# main.net
KiCad netlist of a schematic drawn in Altium Designer
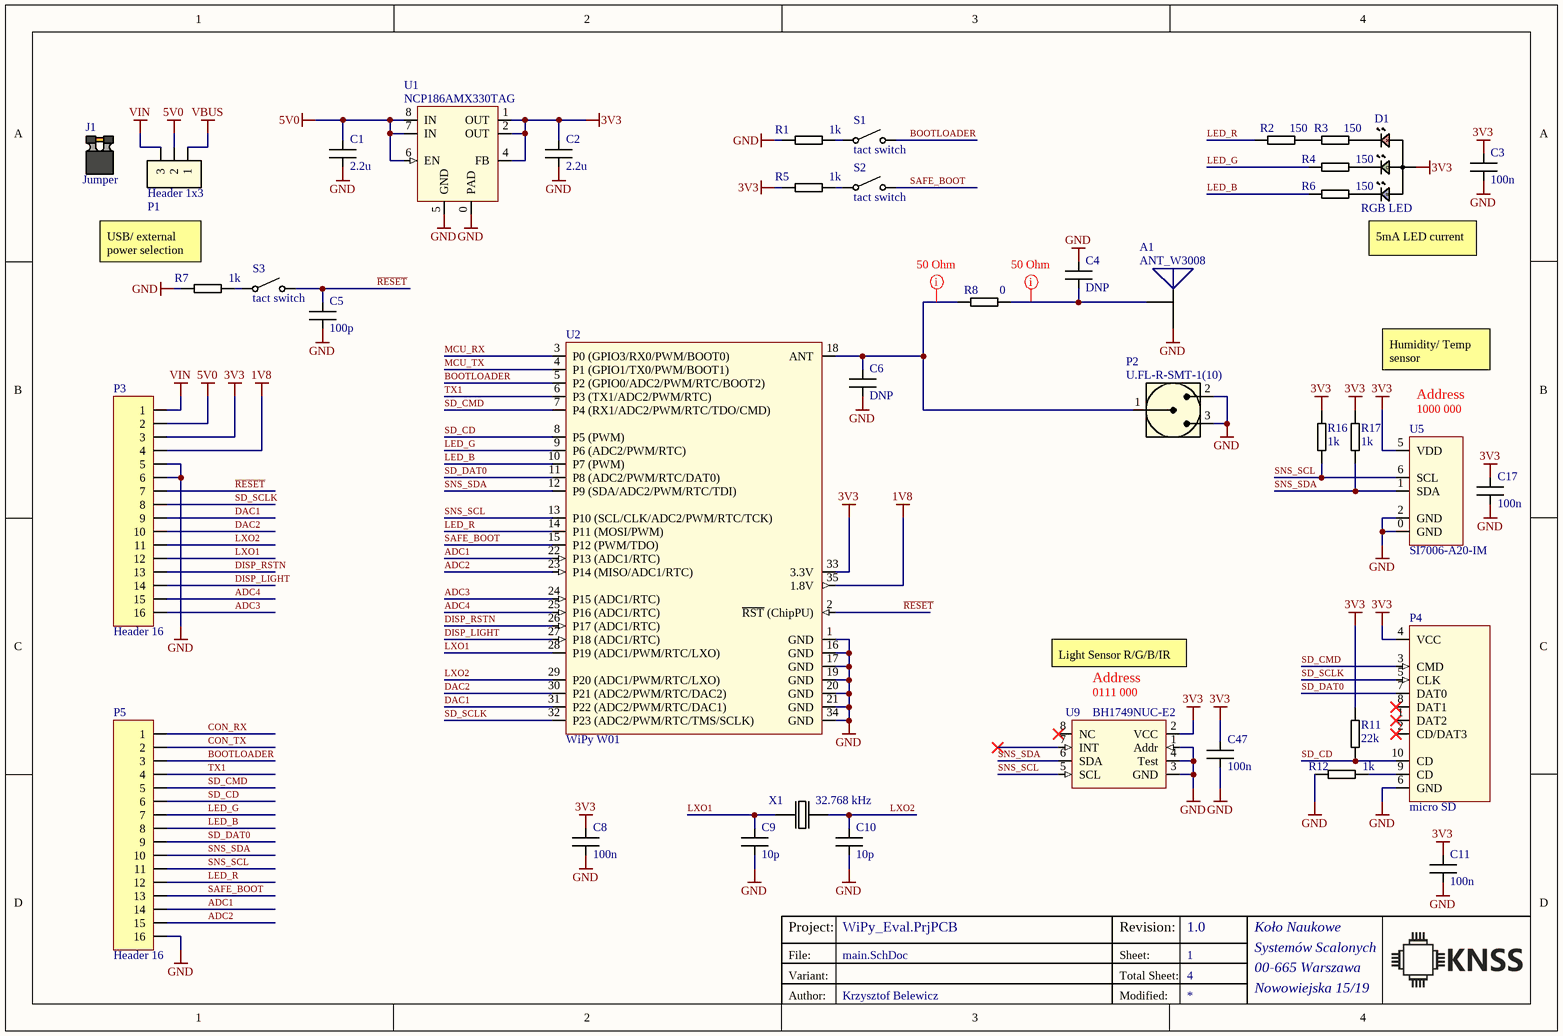
[diagram p0: main.SchDoc]

(export (version "E")
  (design (tool "Eeschema 10.0.6"))
  (components
    (comp (ref "A1")
      (value "ANT_W3008")
      (footprint "W3008")
      (description "Bluetooth / WLAN / WiFi  Ceramic Chip Antenna W x L x H (3.2 x 1.6 x 1.1 mm)")
      (libsource (lib "LIBRARY_SCH") (part "ANT_W3008"))
    )
    (comp (ref "C1")
      (value "2.2u")
      (footprint "CAPC1005N")
      (description "0402 SMD Capacitor")
      (fields (field (name "TOLERANCE") "10%") (field (name "Comment") "Capacitor"))
      (libsource (lib "RLC") (part "Capacitor"))
    )
    (comp (ref "C2")
      (value "2.2u")
      (footprint "CAPC1005N")
      (description "0402 SMD Capacitor")
      (fields (field (name "TOLERANCE") "10%") (field (name "Comment") "Capacitor"))
      (libsource (lib "RLC") (part "Capacitor"))
    )
    (comp (ref "C3")
      (value "100n")
      (footprint "CAPC1005N")
      (description "0402 SMD Capacitor")
      (fields (field (name "TOLERANCE") "10%"))
      (libsource (lib "RLC") (part "Capacitor"))
    )
    (comp (ref "C4")
      (value "DNP")
      (footprint "CAPC1005N")
      (description "0402 SMD Capacitor")
      (fields (field (name "Comment") "Capacitor"))
      (libsource (lib "RLC") (part "Capacitor"))
    )
    (comp (ref "C5")
      (value "100p")
      (footprint "CAPC1005N")
      (description "0402 SMD Capacitor")
      (fields (field (name "TOLERANCE") "10%"))
      (libsource (lib "RLC") (part "Capacitor"))
    )
    (comp (ref "C6")
      (value "DNP")
      (footprint "CAPC1005N")
      (description "0402 SMD Capacitor")
      (fields (field (name "Comment") "Capacitor"))
      (libsource (lib "RLC") (part "Capacitor"))
    )
    (comp (ref "C8")
      (value "100n")
      (footprint "CAPC1005N")
      (description "0402 SMD Capacitor")
      (fields (field (name "TOLERANCE") "10%"))
      (libsource (lib "RLC") (part "Capacitor"))
    )
    (comp (ref "C9")
      (value "10p")
      (footprint "CAPC1005N")
      (description "0402 SMD Capacitor")
      (fields (field (name "TOLERANCE") "5%"))
      (libsource (lib "RLC") (part "Capacitor"))
    )
    (comp (ref "C10")
      (value "10p")
      (footprint "CAPC1005N")
      (description "0402 SMD Capacitor")
      (fields (field (name "TOLERANCE") "5%"))
      (libsource (lib "RLC") (part "Capacitor"))
    )
    (comp (ref "C11")
      (value "100n")
      (footprint "CAPC1005N")
      (description "0402 SMD Capacitor")
      (fields (field (name "TOLERANCE") "10%"))
      (libsource (lib "RLC") (part "Capacitor"))
    )
    (comp (ref "C17")
      (value "100n")
      (footprint "CAPC1005N")
      (description "0402 SMD Capacitor")
      (fields (field (name "TOLERANCE") "10%"))
      (libsource (lib "RLC") (part "Capacitor"))
    )
    (comp (ref "C47")
      (value "100n")
      (footprint "CAPC1005N")
      (description "0402 SMD Capacitor")
      (fields (field (name "TOLERANCE") "10%"))
      (libsource (lib "RLC") (part "Capacitor"))
    )
    (comp (ref "D1")
      (value "RGB LED")
      (footprint "PLCC-4")
      (description "LED; SMD; 3528,PLCC4; RGB; 3,5x2,8x1,9mm; 115°; 20mA; Common anode")
      (libsource (lib "Broadcom_LED") (part "ASMB-MTB1-0A3A2"))
    )
    (comp (ref "J1")
      (value "Jumper")
      (footprint "JUMPER-B")
      (description "1x2, 2.54mm Black header jumper")
      (libsource (lib "Ninigi_Jumpers") (part "Header Jumper Black"))
    )
    (comp (ref "P1")
      (value "Header 1x3")
      (footprint "Header 1x3, Male, 2.54mm, Straight, THT")
      (description "Pin header, 1x3, 2.54mm")
      (libsource (lib "Header") (part "Header 1x3"))
    )
    (comp (ref "P2")
      (value "U.FL-R-SMT-1(10)")
      (footprint "U.FL-R-SMT-1(10)")
      (description "Hirose UFL connector")
      (libsource (lib "Hirose") (part "U.FL-R-SMT-1(10)"))
    )
    (comp (ref "P3")
      (value "Header 16")
      (footprint "HDR1X16")
      (description "Header, 16-Pin")
      (libsource (lib "Miscellaneous Connectors") (part "Header 16"))
    )
    (comp (ref "P4")
      (value "micro SD")
      (footprint "1140084168")
      (description "Memory Card Connectors Micro SD 8 Pin PCB Gold")
      (libsource (lib "Amphenol_uSD") (part "1140084168"))
    )
    (comp (ref "P5")
      (value "Header 16")
      (footprint "HDR1X16")
      (description "Header, 16-Pin")
      (libsource (lib "Miscellaneous Connectors") (part "Header 16"))
    )
    (comp (ref "R1")
      (value "1k")
      (footprint "RESC1005N")
      (description "0402 Film SMD Resistor")
      (fields (field (name "TOLERANCE") "1%") (field (name "POWER") "0.1W"))
      (libsource (lib "RLC") (part "Resistor"))
    )
    (comp (ref "R2")
      (value "150")
      (footprint "RESC1005N")
      (description "0402 Film SMD Resistor")
      (fields (field (name "TOLERANCE") "1%") (field (name "POWER") "0.1W"))
      (libsource (lib "RLC") (part "Resistor"))
    )
    (comp (ref "R3")
      (value "150")
      (footprint "RESC1005N")
      (description "0402 Film SMD Resistor")
      (fields (field (name "TOLERANCE") "1%") (field (name "POWER") "0.1W"))
      (libsource (lib "RLC") (part "Resistor"))
    )
    (comp (ref "R4")
      (value "150")
      (footprint "RESC1005N")
      (description "0402 Film SMD Resistor")
      (fields (field (name "TOLERANCE") "1%") (field (name "POWER") "0.1W"))
      (libsource (lib "RLC") (part "Resistor"))
    )
    (comp (ref "R5")
      (value "1k")
      (footprint "RESC1005N")
      (description "0402 Film SMD Resistor")
      (fields (field (name "TOLERANCE") "1%") (field (name "POWER") "0.1W"))
      (libsource (lib "RLC") (part "Resistor"))
    )
    (comp (ref "R6")
      (value "150")
      (footprint "RESC1005N")
      (description "0402 Film SMD Resistor")
      (fields (field (name "TOLERANCE") "1%") (field (name "POWER") "0.1W"))
      (libsource (lib "RLC") (part "Resistor"))
    )
    (comp (ref "R7")
      (value "1k")
      (footprint "RESC1005N")
      (description "0402 Film SMD Resistor")
      (fields (field (name "TOLERANCE") "1%") (field (name "POWER") "0.1W"))
      (libsource (lib "RLC") (part "Resistor"))
    )
    (comp (ref "R8")
      (value "0")
      (footprint "RESC1005N")
      (description "0402 Film SMD Resistor")
      (fields (field (name "TOLERANCE") "1%") (field (name "POWER") "0.1W"))
      (libsource (lib "RLC") (part "Resistor"))
    )
    (comp (ref "R11")
      (value "22k")
      (footprint "RESC1005N")
      (description "0402 Film SMD Resistor")
      (fields (field (name "TOLERANCE") "1%") (field (name "POWER") "0.1W"))
      (libsource (lib "RLC") (part "Resistor"))
    )
    (comp (ref "R12")
      (value "1k")
      (footprint "RESC1005N")
      (description "0402 Film SMD Resistor")
      (fields (field (name "TOLERANCE") "1%") (field (name "POWER") "0.1W"))
      (libsource (lib "RLC") (part "Resistor"))
    )
    (comp (ref "R16")
      (value "1k")
      (footprint "RESC1005N")
      (description "0402 Film SMD Resistor")
      (fields (field (name "TOLERANCE") "1%") (field (name "POWER") "0.1W"))
      (libsource (lib "RLC") (part "Resistor"))
    )
    (comp (ref "R17")
      (value "1k")
      (footprint "RESC1005N")
      (description "0402 Film SMD Resistor")
      (fields (field (name "TOLERANCE") "1%") (field (name "POWER") "0.1W"))
      (libsource (lib "RLC") (part "Resistor"))
    )
    (comp (ref "S1")
      (value "tact switch")
      (footprint "1301.9319")
      (description "TACT; SPST-NO; 2 position; 0,05A/12VDC; SMT")
      (libsource (lib "Schurter_Switches") (part "1301.9319"))
    )
    (comp (ref "S2")
      (value "tact switch")
      (footprint "1301.9319")
      (description "TACT; SPST-NO; 2 position; 0,05A/12VDC; SMT")
      (libsource (lib "Schurter_Switches") (part "1301.9319"))
    )
    (comp (ref "S3")
      (value "tact switch")
      (footprint "1301.9319")
      (description "TACT; SPST-NO; 2 position; 0,05A/12VDC; SMT")
      (libsource (lib "Schurter_Switches") (part "1301.9319"))
    )
    (comp (ref "U1")
      (value "NCP186AMX330TAG")
      (footprint "XDFN8")
      (description "3.3V 1A LDO Voltage Regulator")
      (libsource (lib "Power_Supervisors") (part "NCP186AMX330TAG"))
    )
    (comp (ref "U2")
      (value "WiPy W01")
      (footprint "WiPy_W01")
      (description "Wireless LAN Module, I2C, I2S, SPI, UART, M2M, Internet of Things")
      (libsource (lib "WiPy") (part "W01"))
    )
    (comp (ref "U5")
      (value "SI7006-A20-IM")
      (footprint "DFN6")
      (description "I2C HUMIDITY AND TEMPERATURE SENSOR")
      (libsource (lib "SiliconLabs") (part "SI7006-A20-IM"))
    )
    (comp (ref "U9")
      (value "BH1749NUC-E2")
      (footprint "WSON-8_Clear")
      (libsource (lib "ROHM") (part "BH1749NUC-E2"))
    )
    (comp (ref "X1")
      (value "32.768 kHz")
      (footprint "MC-306")
      (description "Standard Clock Oscillators 32,768kHz 20ppm -40C +85C")
      (libsource (lib "EPSON_Oscillators") (part "MC306 32.768000KHZ 12.5PF"))
    )
  )
  (nets
    (net (code "1") (name "/ADC1") (class "Default")
      (node (ref "P5") (pin "14") (pinfunction "14_14") (pintype "passive"))
      (node (ref "U2") (pin "22") (pinfunction "P13_(ADC1/RTC)_22") (pintype "input"))
    )
    (net (code "2") (name "/ADC2") (class "Default")
      (node (ref "P5") (pin "15") (pinfunction "15_15") (pintype "passive"))
      (node (ref "U2") (pin "23") (pinfunction "P14_(MISO/ADC1/RTC)_23") (pintype "input"))
    )
    (net (code "3") (name "/ADC3") (class "Default")
      (node (ref "P3") (pin "16") (pinfunction "16_16") (pintype "passive"))
      (node (ref "U2") (pin "24") (pinfunction "P15_(ADC1/RTC)_24") (pintype "input"))
    )
    (net (code "4") (name "/ADC4") (class "Default")
      (node (ref "P3") (pin "15") (pinfunction "15_15") (pintype "passive"))
      (node (ref "U2") (pin "25") (pinfunction "P16_(ADC1/RTC)_25") (pintype "input"))
    )
    (net (code "5") (name "/BOOTLOADER") (class "Default")
      (node (ref "P5") (pin "3") (pinfunction "3_3") (pintype "passive"))
      (node (ref "S1") (pin "2") (pinfunction "2_2") (pintype "passive"))
      (node (ref "U2") (pin "5") (pinfunction "P2_(GPIO0/ADC2/PWM/RTC/BOOT2)_5") (pintype "bidirectional"))
    )
    (net (code "6") (name "/CON_RX") (class "Default")
      (node (ref "P5") (pin "1") (pinfunction "1_1") (pintype "passive"))
    )
    (net (code "7") (name "/CON_TX") (class "Default")
      (node (ref "P5") (pin "2") (pinfunction "2_2") (pintype "passive"))
    )
    (net (code "8") (name "/DAC1") (class "Default")
      (node (ref "P3") (pin "9") (pinfunction "9_9") (pintype "passive"))
      (node (ref "U2") (pin "31") (pinfunction "P22_(ADC2/PWM/RTC/DAC1)_31") (pintype "bidirectional"))
    )
    (net (code "9") (name "/DAC2") (class "Default")
      (node (ref "P3") (pin "10") (pinfunction "10_10") (pintype "passive"))
      (node (ref "U2") (pin "30") (pinfunction "P21_(ADC2/PWM/RTC/DAC2)_30") (pintype "bidirectional"))
    )
    (net (code "10") (name "/DISP_LIGHT") (class "Default")
      (node (ref "P3") (pin "14") (pinfunction "14_14") (pintype "passive"))
      (node (ref "U2") (pin "27") (pinfunction "P18_(ADC1/RTC)_27") (pintype "input"))
    )
    (net (code "11") (name "/DISP_RSTN") (class "Default")
      (node (ref "P3") (pin "13") (pinfunction "13_13") (pintype "passive"))
      (node (ref "U2") (pin "26") (pinfunction "P17_(ADC1/RTC)_26") (pintype "input"))
    )
    (net (code "12") (name "/LED_B") (class "Default")
      (node (ref "P5") (pin "8") (pinfunction "8_8") (pintype "passive"))
      (node (ref "R6") (pin "2") (pinfunction "2_2") (pintype "passive"))
      (node (ref "U2") (pin "10") (pinfunction "P7_(PWM)_10") (pintype "bidirectional"))
    )
    (net (code "13") (name "/LED_G") (class "Default")
      (node (ref "P5") (pin "7") (pinfunction "7_7") (pintype "passive"))
      (node (ref "R4") (pin "2") (pinfunction "2_2") (pintype "passive"))
      (node (ref "U2") (pin "9") (pinfunction "P6_(ADC2/PWM/RTC)_9") (pintype "bidirectional"))
    )
    (net (code "14") (name "/LED_R") (class "Default")
      (node (ref "P5") (pin "12") (pinfunction "12_12") (pintype "passive"))
      (node (ref "R2") (pin "2") (pinfunction "2_2") (pintype "passive"))
      (node (ref "U2") (pin "14") (pinfunction "P11_(MOSI/PWM)_14") (pintype "bidirectional"))
    )
    (net (code "15") (name "/LXO1") (class "Default")
      (node (ref "C9") (pin "2") (pinfunction "2_2") (pintype "passive"))
      (node (ref "P3") (pin "12") (pinfunction "12_12") (pintype "passive"))
      (node (ref "U2") (pin "28") (pinfunction "P19_(ADC1/PWM/RTC/LXO)_28") (pintype "bidirectional"))
      (node (ref "X1") (pin "4") (pinfunction "4_4") (pintype "passive"))
    )
    (net (code "16") (name "/LXO2") (class "Default")
      (node (ref "C10") (pin "2") (pinfunction "2_2") (pintype "passive"))
      (node (ref "P3") (pin "11") (pinfunction "11_11") (pintype "passive"))
      (node (ref "U2") (pin "29") (pinfunction "P20_(ADC1/PWM/RTC/LXO)_29") (pintype "bidirectional"))
      (node (ref "X1") (pin "1") (pinfunction "1_1") (pintype "passive"))
    )
    (net (code "17") (name "/MCU_RX") (class "Default")
      (node (ref "U2") (pin "3") (pinfunction "P0_(GPIO3/RX0/PWM/BOOT0)_3") (pintype "bidirectional"))
    )
    (net (code "18") (name "/MCU_TX") (class "Default")
      (node (ref "U2") (pin "4") (pinfunction "P1_(GPIO1/TX0/PWM/BOOT1)_4") (pintype "bidirectional"))
    )
    (net (code "19") (name "/SAFE_BOOT") (class "Default")
      (node (ref "P5") (pin "13") (pinfunction "13_13") (pintype "passive"))
      (node (ref "S2") (pin "2") (pinfunction "2_2") (pintype "passive"))
      (node (ref "U2") (pin "15") (pinfunction "P12_(PWM/TDO)_15") (pintype "bidirectional"))
    )
    (net (code "20") (name "/SD_CD") (class "Default")
      (node (ref "P4") (pin "10") (pinfunction "CD_10") (pintype "passive"))
      (node (ref "P5") (pin "6") (pinfunction "6_6") (pintype "passive"))
      (node (ref "R11") (pin "1") (pinfunction "1_1") (pintype "passive"))
      (node (ref "U2") (pin "8") (pinfunction "P5_(PWM)_8") (pintype "bidirectional"))
    )
    (net (code "21") (name "/SD_CMD") (class "Default")
      (node (ref "P4") (pin "3") (pinfunction "CMD_3") (pintype "input"))
      (node (ref "P5") (pin "5") (pinfunction "5_5") (pintype "passive"))
      (node (ref "U2") (pin "7") (pinfunction "P4_(RX1/ADC2/PWM/RTC/TDO/CMD)_7") (pintype "bidirectional"))
    )
    (net (code "22") (name "/SD_DAT0") (class "Default")
      (node (ref "P4") (pin "7") (pinfunction "DAT0_7") (pintype "bidirectional"))
      (node (ref "P5") (pin "9") (pinfunction "9_9") (pintype "passive"))
      (node (ref "U2") (pin "11") (pinfunction "P8_(ADC2/PWM/RTC/DAT0)_11") (pintype "bidirectional"))
    )
    (net (code "23") (name "/SD_SCLK") (class "Default")
      (node (ref "P3") (pin "8") (pinfunction "8_8") (pintype "passive"))
      (node (ref "P4") (pin "5") (pinfunction "CLK_5") (pintype "input"))
      (node (ref "U2") (pin "32") (pinfunction "P23_(ADC2/PWM/RTC/TMS/SCLK)_32") (pintype "bidirectional"))
    )
    (net (code "24") (name "/SNS_SCL") (class "Default")
      (node (ref "P5") (pin "11") (pinfunction "11_11") (pintype "passive"))
      (node (ref "R16") (pin "2") (pinfunction "2_2") (pintype "passive"))
      (node (ref "U2") (pin "13") (pinfunction "P10_(SCL/CLK/ADC2/PWM/RTC/TCK)_13") (pintype "bidirectional"))
      (node (ref "U5") (pin "6") (pinfunction "SCL_6") (pintype "bidirectional"))
      (node (ref "U9") (pin "5") (pinfunction "SCL_5") (pintype "input"))
    )
    (net (code "25") (name "/SNS_SDA") (class "Default")
      (node (ref "P5") (pin "10") (pinfunction "10_10") (pintype "passive"))
      (node (ref "R17") (pin "2") (pinfunction "2_2") (pintype "passive"))
      (node (ref "U2") (pin "12") (pinfunction "P9_(SDA/ADC2/PWM/RTC/TDI)_12") (pintype "bidirectional"))
      (node (ref "U5") (pin "1") (pinfunction "SDA_1") (pintype "bidirectional"))
      (node (ref "U9") (pin "6") (pinfunction "SDA_6") (pintype "bidirectional"))
    )
    (net (code "26") (name "/TX1") (class "Default")
      (node (ref "P5") (pin "4") (pinfunction "4_4") (pintype "passive"))
      (node (ref "U2") (pin "6") (pinfunction "P3_(TX1/ADC2/PWM/RTC)_6") (pintype "bidirectional"))
    )
    (net (code "27") (name "/~{RESET}") (class "Default")
      (node (ref "C5") (pin "2") (pinfunction "2_2") (pintype "passive"))
      (node (ref "P3") (pin "7") (pinfunction "7_7") (pintype "passive"))
      (node (ref "S3") (pin "2") (pinfunction "2_2") (pintype "passive"))
      (node (ref "U2") (pin "2") (pinfunction "~{RST}_(ChipPU)_2") (pintype "input"))
    )
    (net (code "28") (name "1V8") (class "Default")
      (node (ref "P3") (pin "4") (pinfunction "4_4") (pintype "passive"))
      (node (ref "U2") (pin "35") (pinfunction "1.8V_35") (pintype "output"))
    )
    (net (code "29") (name "3V3") (class "Default")
      (node (ref "C11") (pin "2") (pinfunction "2_2") (pintype "passive"))
      (node (ref "C17") (pin "2") (pinfunction "2_2") (pintype "passive"))
      (node (ref "C2") (pin "2") (pinfunction "2_2") (pintype "passive"))
      (node (ref "C3") (pin "2") (pinfunction "2_2") (pintype "passive"))
      (node (ref "C47") (pin "2") (pinfunction "2_2") (pintype "passive"))
      (node (ref "C8") (pin "2") (pinfunction "2_2") (pintype "passive"))
      (node (ref "D1") (pin "4") (pinfunction "A_4") (pintype "passive"))
      (node (ref "P3") (pin "3") (pinfunction "3_3") (pintype "passive"))
      (node (ref "P4") (pin "4") (pinfunction "VCC_4") (pintype "power_in"))
      (node (ref "R11") (pin "2") (pinfunction "2_2") (pintype "passive"))
      (node (ref "R16") (pin "1") (pinfunction "1_1") (pintype "passive"))
      (node (ref "R17") (pin "1") (pinfunction "1_1") (pintype "passive"))
      (node (ref "R5") (pin "2") (pinfunction "2_2") (pintype "passive"))
      (node (ref "U1") (pin "1") (pinfunction "OUT_1") (pintype "power_in"))
      (node (ref "U1") (pin "2") (pinfunction "OUT_2") (pintype "power_in"))
      (node (ref "U1") (pin "4") (pinfunction "FB_4") (pintype "power_in"))
      (node (ref "U2") (pin "33") (pinfunction "3.3V_33") (pintype "power_in"))
      (node (ref "U5") (pin "5") (pinfunction "VDD_5") (pintype "power_in"))
      (node (ref "U9") (pin "2") (pinfunction "VCC_2") (pintype "power_in"))
    )
    (net (code "30") (name "5V0") (class "Default")
      (node (ref "C1") (pin "2") (pinfunction "2_2") (pintype "passive"))
      (node (ref "P1") (pin "2") (pinfunction "2_2") (pintype "passive"))
      (node (ref "P3") (pin "2") (pinfunction "2_2") (pintype "passive"))
      (node (ref "U1") (pin "6") (pinfunction "EN_6") (pintype "input"))
      (node (ref "U1") (pin "7") (pinfunction "IN_7") (pintype "power_in"))
      (node (ref "U1") (pin "8") (pinfunction "IN_8") (pintype "power_in"))
    )
    (net (code "31") (name "GND") (class "Default")
      (node (ref "A1") (pin "2") (pinfunction "GND_2") (pintype "passive"))
      (node (ref "C1") (pin "1") (pinfunction "1_1") (pintype "passive"))
      (node (ref "C10") (pin "1") (pinfunction "1_1") (pintype "passive"))
      (node (ref "C11") (pin "1") (pinfunction "1_1") (pintype "passive"))
      (node (ref "C17") (pin "1") (pinfunction "1_1") (pintype "passive"))
      (node (ref "C2") (pin "1") (pinfunction "1_1") (pintype "passive"))
      (node (ref "C3") (pin "1") (pinfunction "1_1") (pintype "passive"))
      (node (ref "C4") (pin "2") (pinfunction "2_2") (pintype "passive"))
      (node (ref "C47") (pin "1") (pinfunction "1_1") (pintype "passive"))
      (node (ref "C5") (pin "1") (pinfunction "1_1") (pintype "passive"))
      (node (ref "C6") (pin "1") (pinfunction "1_1") (pintype "passive"))
      (node (ref "C8") (pin "1") (pinfunction "1_1") (pintype "passive"))
      (node (ref "C9") (pin "1") (pinfunction "1_1") (pintype "passive"))
      (node (ref "P2") (pin "2") (pinfunction "2_2") (pintype "passive"))
      (node (ref "P2") (pin "3") (pinfunction "3_3") (pintype "passive"))
      (node (ref "P3") (pin "5") (pinfunction "5_5") (pintype "passive"))
      (node (ref "P3") (pin "6") (pinfunction "6_6") (pintype "passive"))
      (node (ref "P4") (pin "6") (pinfunction "GND_6") (pintype "power_in"))
      (node (ref "P5") (pin "16") (pinfunction "16_16") (pintype "passive"))
      (node (ref "R1") (pin "2") (pinfunction "2_2") (pintype "passive"))
      (node (ref "R12") (pin "2") (pinfunction "2_2") (pintype "passive"))
      (node (ref "R7") (pin "2") (pinfunction "2_2") (pintype "passive"))
      (node (ref "U1") (pin "0") (pinfunction "PAD_0") (pintype "power_in"))
      (node (ref "U1") (pin "5") (pinfunction "GND_5") (pintype "power_in"))
      (node (ref "U2") (pin "1") (pinfunction "GND_1") (pintype "power_in"))
      (node (ref "U2") (pin "16") (pinfunction "GND_16") (pintype "power_in"))
      (node (ref "U2") (pin "17") (pinfunction "GND_17") (pintype "power_in"))
      (node (ref "U2") (pin "19") (pinfunction "GND_19") (pintype "power_in"))
      (node (ref "U2") (pin "20") (pinfunction "GND_20") (pintype "power_in"))
      (node (ref "U2") (pin "21") (pinfunction "GND_21") (pintype "power_in"))
      (node (ref "U2") (pin "34") (pinfunction "GND_34") (pintype "power_in"))
      (node (ref "U5") (pin "0") (pinfunction "GND_0") (pintype "power_in"))
      (node (ref "U5") (pin "2") (pinfunction "GND_2") (pintype "power_in"))
      (node (ref "U9") (pin "1") (pinfunction "Addr_1") (pintype "input"))
      (node (ref "U9") (pin "3") (pinfunction "GND_3") (pintype "power_in"))
      (node (ref "U9") (pin "4") (pinfunction "Test_4") (pintype "power_in"))
    )
    (net (code "32") (name "Net-(A1-SIG)") (class "Default")
      (node (ref "A1") (pin "1") (pinfunction "SIG_1") (pintype "passive"))
      (node (ref "C4") (pin "1") (pinfunction "1_1") (pintype "passive"))
      (node (ref "R8") (pin "1") (pinfunction "1_1") (pintype "passive"))
    )
    (net (code "33") (name "Net-(D1-CB)") (class "Default")
      (node (ref "D1") (pin "3") (pinfunction "CB_3") (pintype "passive"))
      (node (ref "R6") (pin "1") (pinfunction "1_1") (pintype "passive"))
    )
    (net (code "34") (name "Net-(D1-CG)") (class "Default")
      (node (ref "D1") (pin "2") (pinfunction "CG_2") (pintype "passive"))
      (node (ref "R4") (pin "1") (pinfunction "1_1") (pintype "passive"))
    )
    (net (code "35") (name "Net-(D1-CR)") (class "Default")
      (node (ref "D1") (pin "1") (pinfunction "CR_1") (pintype "passive"))
      (node (ref "R3") (pin "1") (pinfunction "1_1") (pintype "passive"))
    )
    (net (code "36") (name "Net-(P4-CD-Pad9)") (class "Default")
      (node (ref "P4") (pin "9") (pinfunction "CD_9") (pintype "passive"))
      (node (ref "R12") (pin "1") (pinfunction "1_1") (pintype "passive"))
    )
    (net (code "37") (name "Net-(R1-Pad1)") (class "Default")
      (node (ref "R1") (pin "1") (pinfunction "1_1") (pintype "passive"))
      (node (ref "S1") (pin "1") (pinfunction "1_1") (pintype "passive"))
    )
    (net (code "38") (name "Net-(R2-Pad1)") (class "Default")
      (node (ref "R2") (pin "1") (pinfunction "1_1") (pintype "passive"))
      (node (ref "R3") (pin "2") (pinfunction "2_2") (pintype "passive"))
    )
    (net (code "39") (name "Net-(R5-Pad1)") (class "Default")
      (node (ref "R5") (pin "1") (pinfunction "1_1") (pintype "passive"))
      (node (ref "S2") (pin "1") (pinfunction "1_1") (pintype "passive"))
    )
    (net (code "40") (name "Net-(R7-Pad1)") (class "Default")
      (node (ref "R7") (pin "1") (pinfunction "1_1") (pintype "passive"))
      (node (ref "S3") (pin "1") (pinfunction "1_1") (pintype "passive"))
    )
    (net (code "41") (name "Net-(U2-ANT)") (class "Default")
      (node (ref "C6") (pin "2") (pinfunction "2_2") (pintype "passive"))
      (node (ref "P2") (pin "1") (pinfunction "1_1") (pintype "passive"))
      (node (ref "R8") (pin "2") (pinfunction "2_2") (pintype "passive"))
      (node (ref "U2") (pin "18") (pinfunction "ANT_18") (pintype "bidirectional"))
    )
    (net (code "42") (name "VBUS") (class "Default")
      (node (ref "P1") (pin "1") (pinfunction "1_1") (pintype "passive"))
    )
    (net (code "43") (name "VIN") (class "Default")
      (node (ref "P1") (pin "3") (pinfunction "3_3") (pintype "passive"))
      (node (ref "P3") (pin "1") (pinfunction "1_1") (pintype "passive"))
    )
    (net (code "44") (name "unconnected-(P4-CD{slash}DAT3-Pad2)") (class "Default")
      (node (ref "P4") (pin "2") (pinfunction "CD/DAT3_2") (pintype "bidirectional+no_connect"))
    )
    (net (code "45") (name "unconnected-(P4-DAT1-Pad8)") (class "Default")
      (node (ref "P4") (pin "8") (pinfunction "DAT1_8") (pintype "bidirectional+no_connect"))
    )
    (net (code "46") (name "unconnected-(P4-DAT2-Pad1)") (class "Default")
      (node (ref "P4") (pin "1") (pinfunction "DAT2_1") (pintype "bidirectional+no_connect"))
    )
    (net (code "47") (name "unconnected-(U9-INT-Pad7)") (class "Default")
      (node (ref "U9") (pin "7") (pinfunction "INT_7") (pintype "input+no_connect"))
    )
    (net (code "48") (name "unconnected-(U9-NC-Pad8)") (class "Default")
      (node (ref "U9") (pin "8") (pinfunction "NC_8") (pintype "passive+no_connect"))
    )
  )
)
